# czujnik_smrodu_esp_v02.net
KiCad netlist of a schematic drawn in EAGLE
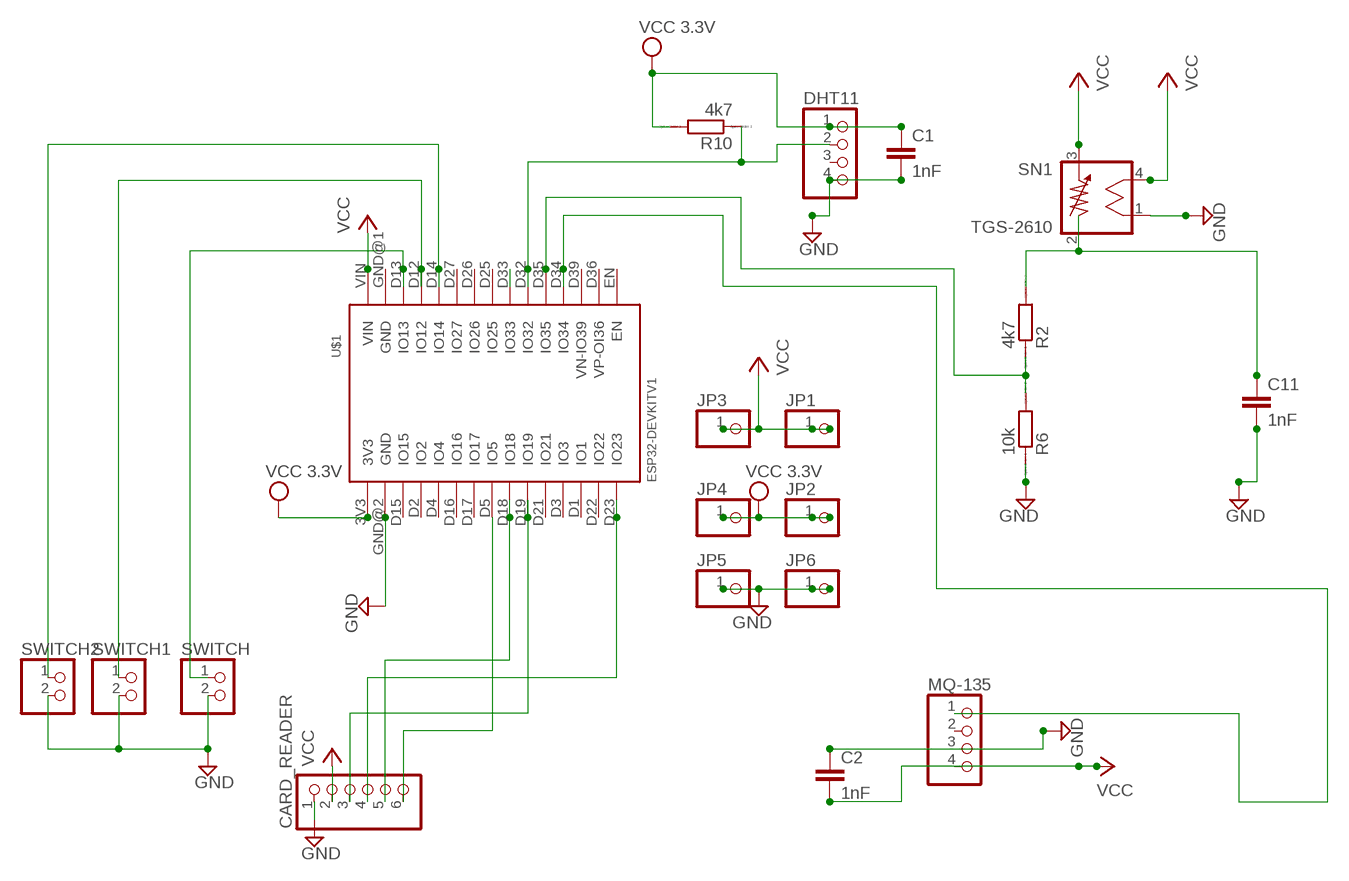
[diagram p0: schematic, sheet 1]

(export (version "E")
  (design (tool "Eeschema 10.0.6"))
  (components
    (comp (ref "C1")
      (value "1nF")
      (footprint "eagle-import:C2.5-3")
      (libsource (lib "eagle-import") (part "C2,5-3"))
    )
    (comp (ref "C2")
      (value "1nF")
      (footprint "eagle-import:C2.5-3")
      (libsource (lib "eagle-import") (part "C2,5-3"))
    )
    (comp (ref "C11")
      (value "1nF")
      (footprint "eagle-import:C2.5-3")
      (libsource (lib "eagle-import") (part "C2,5-3"))
    )
    (comp (ref "CARD_READER")
      (value "PINHD-1X6")
      (footprint "eagle-import:1X06")
      (libsource (lib "eagle-import") (part "PINHD-1X6"))
    )
    (comp (ref "DHT11")
      (value "PINHD-1X4")
      (footprint "eagle-import:1X04")
      (libsource (lib "eagle-import") (part "PINHD-1X4"))
    )
    (comp (ref "JP1")
      (value "PINHD-1X1")
      (footprint "eagle-import:1X01")
      (libsource (lib "eagle-import") (part "PINHD-1X1"))
    )
    (comp (ref "JP2")
      (value "PINHD-1X1")
      (footprint "eagle-import:1X01")
      (libsource (lib "eagle-import") (part "PINHD-1X1"))
    )
    (comp (ref "JP3")
      (value "PINHD-1X1")
      (footprint "eagle-import:1X01")
      (libsource (lib "eagle-import") (part "PINHD-1X1"))
    )
    (comp (ref "JP4")
      (value "PINHD-1X1")
      (footprint "eagle-import:1X01")
      (libsource (lib "eagle-import") (part "PINHD-1X1"))
    )
    (comp (ref "JP5")
      (value "PINHD-1X1")
      (footprint "eagle-import:1X01")
      (libsource (lib "eagle-import") (part "PINHD-1X1"))
    )
    (comp (ref "JP6")
      (value "PINHD-1X1")
      (footprint "eagle-import:1X01")
      (libsource (lib "eagle-import") (part "PINHD-1X1"))
    )
    (comp (ref "MQ-135")
      (value "PINHD-1X4")
      (footprint "eagle-import:1X04")
      (libsource (lib "eagle-import") (part "PINHD-1X4"))
    )
    (comp (ref "R2")
      (value "4k7")
      (footprint "eagle-import:0207_10")
      (libsource (lib "eagle-import") (part "R0207/10"))
    )
    (comp (ref "R6")
      (value "10k")
      (footprint "eagle-import:0207_10")
      (libsource (lib "eagle-import") (part "R0207/10"))
    )
    (comp (ref "R10")
      (value "4k7")
      (footprint "eagle-import:0207_10")
      (libsource (lib "eagle-import") (part "R0207/10"))
    )
    (comp (ref "SN1")
      (value "TGS-2610")
      (footprint "eagle-import:TGS-2610")
      (libsource (lib "eagle-import") (part "TGS-2610"))
    )
    (comp (ref "SWITCH")
      (value "PINHD-1X2")
      (footprint "eagle-import:1X02")
      (libsource (lib "eagle-import") (part "PINHD-1X2"))
    )
    (comp (ref "SWITCH1")
      (value "PINHD-1X2")
      (footprint "eagle-import:1X02")
      (libsource (lib "eagle-import") (part "PINHD-1X2"))
    )
    (comp (ref "SWITCH2")
      (value "PINHD-1X2")
      (footprint "eagle-import:1X02")
      (libsource (lib "eagle-import") (part "PINHD-1X2"))
    )
    (comp (ref "U$1")
      (value "ESP32DEVKITV1")
      (footprint "eagle-import:ESP32-DEVKITV1")
      (libsource (lib "eagle-import") (part "ESP32DEVKITV1"))
    )
  )
  (nets
    (net (code "1") (name "GND") (class "Default")
      (node (ref "C1") (pin "2") (pinfunction "2_2") (pintype "passive"))
      (node (ref "C11") (pin "2") (pinfunction "2_2") (pintype "passive"))
      (node (ref "C2") (pin "1") (pinfunction "1_1") (pintype "passive"))
      (node (ref "CARD_READER") (pin "1") (pinfunction "1_1") (pintype "passive"))
      (node (ref "DHT11") (pin "4") (pinfunction "4_4") (pintype "passive"))
      (node (ref "JP5") (pin "1") (pinfunction "1_1") (pintype "passive"))
      (node (ref "JP6") (pin "1") (pinfunction "1_1") (pintype "passive"))
      (node (ref "MQ-135") (pin "3") (pinfunction "3_3") (pintype "passive"))
      (node (ref "R6") (pin "1") (pinfunction "1_1") (pintype "passive"))
      (node (ref "SN1") (pin "1") (pinfunction "1_1") (pintype "passive"))
      (node (ref "SWITCH") (pin "2") (pinfunction "2_2") (pintype "passive"))
      (node (ref "SWITCH1") (pin "2") (pinfunction "2_2") (pintype "passive"))
      (node (ref "SWITCH2") (pin "2") (pinfunction "2_2") (pintype "passive"))
      (node (ref "U$1") (pin "GND@2") (pinfunction "GND_GND@2") (pintype "bidirectional"))
    )
    (net (code "2") (name "Net-(C11-Pad1)") (class "Default")
      (node (ref "C11") (pin "1") (pinfunction "1_1") (pintype "passive"))
      (node (ref "R2") (pin "2") (pinfunction "2_2") (pintype "passive"))
      (node (ref "SN1") (pin "2") (pinfunction "2_2") (pintype "passive"))
    )
    (net (code "3") (name "Net-(U$1-IO5)") (class "Default")
      (node (ref "CARD_READER") (pin "6") (pinfunction "6_6") (pintype "passive"))
      (node (ref "U$1") (pin "D5") (pinfunction "IO5_D5") (pintype "bidirectional"))
    )
    (net (code "4") (name "Net-(U$1-IO12)") (class "Default")
      (node (ref "SWITCH1") (pin "1") (pinfunction "1_1") (pintype "passive"))
      (node (ref "U$1") (pin "D12") (pinfunction "IO12_D12") (pintype "bidirectional"))
    )
    (net (code "5") (name "Net-(U$1-IO13)") (class "Default")
      (node (ref "SWITCH") (pin "1") (pinfunction "1_1") (pintype "passive"))
      (node (ref "U$1") (pin "D13") (pinfunction "IO13_D13") (pintype "bidirectional"))
    )
    (net (code "6") (name "Net-(U$1-IO14)") (class "Default")
      (node (ref "SWITCH2") (pin "1") (pinfunction "1_1") (pintype "passive"))
      (node (ref "U$1") (pin "D14") (pinfunction "IO14_D14") (pintype "bidirectional"))
    )
    (net (code "7") (name "Net-(U$1-IO18)") (class "Default")
      (node (ref "CARD_READER") (pin "5") (pinfunction "5_5") (pintype "passive"))
      (node (ref "U$1") (pin "D18") (pinfunction "IO18_D18") (pintype "bidirectional"))
    )
    (net (code "8") (name "Net-(U$1-IO19)") (class "Default")
      (node (ref "CARD_READER") (pin "3") (pinfunction "3_3") (pintype "passive"))
      (node (ref "U$1") (pin "D19") (pinfunction "IO19_D19") (pintype "bidirectional"))
    )
    (net (code "9") (name "Net-(U$1-IO23)") (class "Default")
      (node (ref "CARD_READER") (pin "4") (pinfunction "4_4") (pintype "passive"))
      (node (ref "U$1") (pin "D23") (pinfunction "IO23_D23") (pintype "bidirectional"))
    )
    (net (code "10") (name "Net-(U$1-IO32)") (class "Default")
      (node (ref "DHT11") (pin "2") (pinfunction "2_2") (pintype "passive"))
      (node (ref "R10") (pin "1") (pinfunction "1_1") (pintype "passive"))
      (node (ref "U$1") (pin "D32") (pinfunction "IO32_D32") (pintype "bidirectional"))
    )
    (net (code "11") (name "Net-(U$1-IO34)") (class "Default")
      (node (ref "MQ-135") (pin "1") (pinfunction "1_1") (pintype "passive"))
      (node (ref "U$1") (pin "D34") (pinfunction "IO34_D34") (pintype "bidirectional"))
    )
    (net (code "12") (name "Net-(U$1-IO35)") (class "Default")
      (node (ref "R2") (pin "1") (pinfunction "1_1") (pintype "passive"))
      (node (ref "R6") (pin "2") (pinfunction "2_2") (pintype "passive"))
      (node (ref "U$1") (pin "D35") (pinfunction "IO35_D35") (pintype "bidirectional"))
    )
    (net (code "13") (name "VCC") (class "Default")
      (node (ref "C1") (pin "1") (pinfunction "1_1") (pintype "passive"))
      (node (ref "C2") (pin "2") (pinfunction "2_2") (pintype "passive"))
      (node (ref "CARD_READER") (pin "2") (pinfunction "2_2") (pintype "passive"))
      (node (ref "DHT11") (pin "1") (pinfunction "1_1") (pintype "passive"))
      (node (ref "JP1") (pin "1") (pinfunction "1_1") (pintype "passive"))
      (node (ref "JP2") (pin "1") (pinfunction "1_1") (pintype "passive"))
      (node (ref "JP3") (pin "1") (pinfunction "1_1") (pintype "passive"))
      (node (ref "JP4") (pin "1") (pinfunction "1_1") (pintype "passive"))
      (node (ref "MQ-135") (pin "4") (pinfunction "4_4") (pintype "passive"))
      (node (ref "R10") (pin "2") (pinfunction "2_2") (pintype "passive"))
      (node (ref "SN1") (pin "3") (pinfunction "3_3") (pintype "passive"))
      (node (ref "SN1") (pin "4") (pinfunction "4_4") (pintype "passive"))
      (node (ref "U$1") (pin "3V3") (pinfunction "3V3_3V3") (pintype "bidirectional"))
      (node (ref "U$1") (pin "VIN") (pinfunction "VIN_VIN") (pintype "bidirectional"))
    )
    (net (code "14") (name "unconnected-(DHT11-Pad3)") (class "Default")
      (node (ref "DHT11") (pin "3") (pinfunction "3_3") (pintype "passive"))
    )
    (net (code "15") (name "unconnected-(MQ-135-Pad2)") (class "Default")
      (node (ref "MQ-135") (pin "2") (pinfunction "2_2") (pintype "passive"))
    )
    (net (code "16") (name "unconnected-(U$1-GND-PadGND@1)") (class "Default")
      (node (ref "U$1") (pin "GND@1") (pinfunction "GND_GND@1") (pintype "bidirectional"))
    )
    (net (code "17") (name "unconnected-(U$1-IO1-PadD1)") (class "Default")
      (node (ref "U$1") (pin "D1") (pinfunction "IO1_D1") (pintype "bidirectional"))
    )
    (net (code "18") (name "unconnected-(U$1-IO2-PadD2)") (class "Default")
      (node (ref "U$1") (pin "D2") (pinfunction "IO2_D2") (pintype "bidirectional"))
    )
    (net (code "19") (name "unconnected-(U$1-IO3-PadD3)") (class "Default")
      (node (ref "U$1") (pin "D3") (pinfunction "IO3_D3") (pintype "bidirectional"))
    )
    (net (code "20") (name "unconnected-(U$1-IO4-PadD4)") (class "Default")
      (node (ref "U$1") (pin "D4") (pinfunction "IO4_D4") (pintype "bidirectional"))
    )
    (net (code "21") (name "unconnected-(U$1-IO15-PadD15)") (class "Default")
      (node (ref "U$1") (pin "D15") (pinfunction "IO15_D15") (pintype "bidirectional"))
    )
    (net (code "22") (name "unconnected-(U$1-IO16-PadD16)") (class "Default")
      (node (ref "U$1") (pin "D16") (pinfunction "IO16_D16") (pintype "bidirectional"))
    )
    (net (code "23") (name "unconnected-(U$1-IO17-PadD17)") (class "Default")
      (node (ref "U$1") (pin "D17") (pinfunction "IO17_D17") (pintype "bidirectional"))
    )
    (net (code "24") (name "unconnected-(U$1-IO21-PadD21)") (class "Default")
      (node (ref "U$1") (pin "D21") (pinfunction "IO21_D21") (pintype "bidirectional"))
    )
    (net (code "25") (name "unconnected-(U$1-IO22-PadD22)") (class "Default")
      (node (ref "U$1") (pin "D22") (pinfunction "IO22_D22") (pintype "bidirectional"))
    )
    (net (code "26") (name "unconnected-(U$1-IO25-PadD25)") (class "Default")
      (node (ref "U$1") (pin "D25") (pinfunction "IO25_D25") (pintype "bidirectional"))
    )
    (net (code "27") (name "unconnected-(U$1-IO26-PadD26)") (class "Default")
      (node (ref "U$1") (pin "D26") (pinfunction "IO26_D26") (pintype "bidirectional"))
    )
    (net (code "28") (name "unconnected-(U$1-IO27-PadD27)") (class "Default")
      (node (ref "U$1") (pin "D27") (pinfunction "IO27_D27") (pintype "bidirectional"))
    )
    (net (code "29") (name "unconnected-(U$1-IO33-PadD33)") (class "Default")
      (node (ref "U$1") (pin "D33") (pinfunction "IO33_D33") (pintype "bidirectional"))
    )
    (net (code "30") (name "unconnected-(U$1-PadEN)") (class "Default")
      (node (ref "U$1") (pin "EN") (pinfunction "EN_EN") (pintype "bidirectional"))
    )
    (net (code "31") (name "unconnected-(U$1-VN-IO39-PadD39)") (class "Default")
      (node (ref "U$1") (pin "D39") (pinfunction "VN-IO39_D39") (pintype "bidirectional"))
    )
    (net (code "32") (name "unconnected-(U$1-VP-OI36-PadD36)") (class "Default")
      (node (ref "U$1") (pin "D36") (pinfunction "VP-OI36_D36") (pintype "bidirectional"))
    )
  )
)
